# QPL9503.net
KiCad netlist of a schematic drawn in Altium Designer
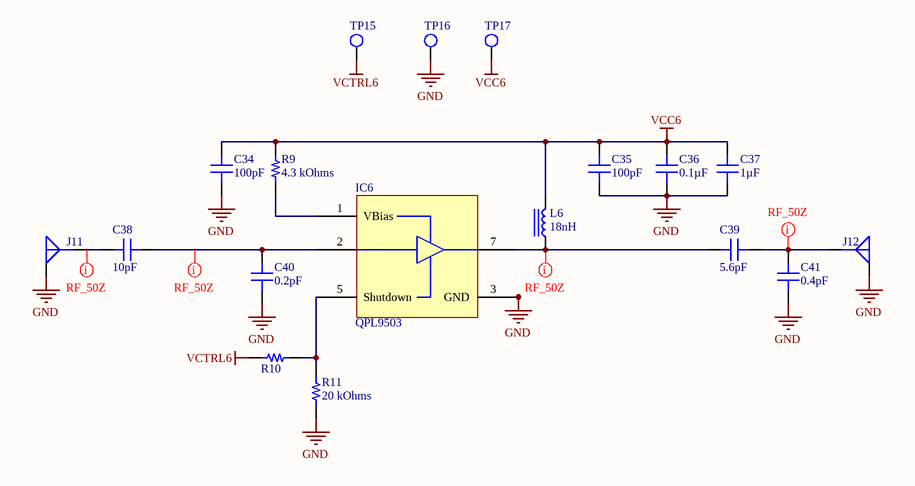
[diagram p0: QPL9503.SchDoc]

(export (version "E")
  (design (tool "Eeschema 10.0.6"))
  (components
    (comp (ref "C34")
      (value "100pF")
      (footprint "CAP 0402_1005")
      (description "CAP CER 100PF 50V C0G/NP0 0402")
      (fields
        (field (name "PART NUMBER") "GCM1555C1H101FA16D")
        (field (name "MANUFACTURER") "Murata Electronics")
      )
      (libsource (lib "Celestial Altium Library - altium_library") (part "Capacitor"))
    )
    (comp (ref "C35")
      (value "100pF")
      (footprint "CAP 0402_1005")
      (description "CAP CER 100PF 50V C0G/NP0 0402")
      (fields
        (field (name "PART NUMBER") "GCM1555C1H101FA16D")
        (field (name "MANUFACTURER") "Murata Electronics")
      )
      (libsource (lib "Celestial Altium Library - altium_library") (part "Capacitor"))
    )
    (comp (ref "C36")
      (value "0.1µF")
      (footprint "CAP 0402_1005")
      (description "CAP CER 0.1UF 16V X7R 0402")
      (fields (field (name "PART NUMBER") "EMK105B7104KV-F") (field (name "MANUFACTURER") "Taiyo Yuden"))
      (libsource (lib "Celestial Altium Library - altium_library") (part "Capacitor"))
    )
    (comp (ref "C37")
      (value "1µF")
      (footprint "CAP 0402_1005")
      (description "CAP CER 1UF 10V X5R 0402")
      (fields
        (field (name "PART NUMBER") "CL05A105KP5NNNC")
        (field (name "MANUFACTURER") "Samsung Electro-Mechanics")
      )
      (libsource (lib "Celestial Altium Library - altium_library") (part "Capacitor"))
    )
    (comp (ref "C38")
      (value "10pF")
      (footprint "CAP 0402_1005 RF")
      (description "CAP CER 10PF 50V C0G/NP0 0402")
      (fields
        (field (name "PART NUMBER") "GJM1555C1H100FB01D")
        (field (name "MANUFACTURER") "Murata Electronics")
      )
      (libsource (lib "Celestial Altium Library - altium_library") (part "Capacitor"))
    )
    (comp (ref "C39")
      (value "5.6pF")
      (footprint "CAP 0402_1005 RF")
      (description "CAP CER 5.6PF 50V C0G/NP0 0402")
      (fields
        (field (name "PART NUMBER") "GJM1555C1H5R6CB01D")
        (field (name "MANUFACTURER") "Murata Electronics")
      )
      (libsource (lib "Celestial Altium Library - altium_library") (part "Capacitor"))
    )
    (comp (ref "C40")
      (value "0.2pF")
      (footprint "CAP 0402_1005 RF")
      (description "CAP CER 0.2PF 50V C0G/NP0 0402")
      (fields
        (field (name "PART NUMBER") "GJM1555C1HR20WB01D")
        (field (name "MANUFACTURER") "Murata Electronics")
      )
      (libsource (lib "Celestial Altium Library - altium_library") (part "Capacitor"))
    )
    (comp (ref "C41")
      (value "0.4pF")
      (footprint "CAP 0402_1005 RF")
      (description "CAP CER 0.4PF 50V C0G/NP0 0402")
      (fields
        (field (name "PART NUMBER") "GJM1555C1HR40BB01D")
        (field (name "MANUFACTURER") "Murata Electronics")
      )
      (libsource (lib "Celestial Altium Library - altium_library") (part "Capacitor"))
    )
    (comp (ref "IC6")
      (value "QPL9503")
      (footprint "Qorvo LNA DFN-8 2X2")
      (description "Ultra Low-Noise, Flat Gain LNA")
      (libsource (lib "IC") (part "QPL9503"))
    )
    (comp (ref "J11")
      (value "CON-SMA-EDGE-S")
      (footprint "CON-SMA-EDGE-S")
      (description "CONN SMA JACK STR EDGE MNT")
      (libsource (lib "Connector") (part "CON-SMA-EDGE-S"))
    )
    (comp (ref "J12")
      (value "CON-SMA-EDGE-S")
      (footprint "CON-SMA-EDGE-S")
      (description "CONN SMA JACK STR EDGE MNT")
      (libsource (lib "Connector") (part "CON-SMA-EDGE-S"))
    )
    (comp (ref "L6")
      (value "18nH")
      (footprint "0402CS")
      (description "Fixed Inductors 1005 18nH Unshld 5% 420mA 230mOhms AECQ2")
      (libsource (lib "Inductor") (part "0402CS-18NXJLW"))
    )
    (comp (ref "R9")
      (value "4.3 kOhms")
      (footprint "RES 0402_1005")
      (description "RES SMD 4.3K OHM 1% 1/16W 0402")
      (fields (field (name "PART NUMBER") "RC0402FR-074K3L") (field (name "MANUFACTURER") "Yageo"))
      (libsource (lib "Celestial Altium Library - altium_library") (part "Resistor"))
    )
    (comp (ref "R10")
      (value "~")
      (footprint "RES 0402_1005")
      (description "RES SMD 0 OHM JUMPER 1/16W 0402")
      (fields (field (name "PART NUMBER") "RC0402JR-070RP") (field (name "MANUFACTURER") "Yageo"))
      (libsource (lib "Celestial Altium Library - altium_library") (part "Resistor"))
    )
    (comp (ref "R11")
      (value "20 kOhms")
      (footprint "RES 0402_1005")
      (description "RES SMD 20K OHM 1% 1/10W 0402")
      (fields
        (field (name "PART NUMBER") "ERJ-2RKF2002X")
        (field (name "MANUFACTURER") "Panasonic Electronic Components")
      )
      (libsource (lib "Celestial Altium Library - altium_library") (part "Resistor"))
    )
    (comp (ref "TP15")
      (value "Test Point-THM")
      (footprint "KEYSTONE-THM-TestPoint")
      (description "THRU HOLE MOUNT TEST POINTS")
      (libsource (lib "Misc") (part "Test Point-THM"))
    )
    (comp (ref "TP16")
      (value "Test Point-THM")
      (footprint "KEYSTONE-THM-TestPoint")
      (description "THRU HOLE MOUNT TEST POINTS")
      (libsource (lib "Misc") (part "Test Point-THM"))
    )
    (comp (ref "TP17")
      (value "Test Point-THM")
      (footprint "KEYSTONE-THM-TestPoint")
      (description "THRU HOLE MOUNT TEST POINTS")
      (libsource (lib "Misc") (part "Test Point-THM"))
    )
  )
  (nets
    (net (code "1") (name "GND") (class "Default")
      (node (ref "C34") (pin "2") (pinfunction "2_2") (pintype "passive"))
      (node (ref "C35") (pin "1") (pinfunction "1_1") (pintype "passive"))
      (node (ref "C36") (pin "1") (pinfunction "1_1") (pintype "passive"))
      (node (ref "C37") (pin "1") (pinfunction "1_1") (pintype "passive"))
      (node (ref "C40") (pin "1") (pinfunction "1_1") (pintype "passive"))
      (node (ref "C41") (pin "1") (pinfunction "1_1") (pintype "passive"))
      (node (ref "IC6") (pin "3") (pinfunction "GND_3") (pintype "passive"))
      (node (ref "IC6") (pin "4") (pinfunction "GND_4") (pintype "passive"))
      (node (ref "IC6") (pin "6") (pinfunction "GND_6") (pintype "passive"))
      (node (ref "IC6") (pin "8") (pinfunction "GND_8") (pintype "passive"))
      (node (ref "IC6") (pin "9") (pinfunction "GND_9") (pintype "passive"))
      (node (ref "J11") (pin "2") (pinfunction "G_2") (pintype "passive"))
      (node (ref "J12") (pin "2") (pinfunction "G_2") (pintype "passive"))
      (node (ref "R11") (pin "1") (pinfunction "1_1") (pintype "passive"))
      (node (ref "TP16") (pin "1") (pinfunction "TP_1") (pintype "passive"))
    )
    (net (code "2") (name "Net-(IC6-IN)") (class "Default")
      (node (ref "C38") (pin "2") (pinfunction "2_2") (pintype "passive"))
      (node (ref "C40") (pin "2") (pinfunction "2_2") (pintype "passive"))
      (node (ref "IC6") (pin "2") (pinfunction "IN_2") (pintype "passive"))
    )
    (net (code "3") (name "Net-(IC6-OUT)") (class "Default")
      (node (ref "C39") (pin "1") (pinfunction "1_1") (pintype "passive"))
      (node (ref "IC6") (pin "7") (pinfunction "OUT_7") (pintype "passive"))
      (node (ref "L6") (pin "1") (pinfunction "1_1") (pintype "passive"))
    )
    (net (code "4") (name "Net-(IC6-Shutdown)") (class "Default")
      (node (ref "IC6") (pin "5") (pinfunction "Shutdown_5") (pintype "passive"))
      (node (ref "R10") (pin "2") (pinfunction "2_2") (pintype "passive"))
      (node (ref "R11") (pin "2") (pinfunction "2_2") (pintype "passive"))
    )
    (net (code "5") (name "Net-(IC6-VBias)") (class "Default")
      (node (ref "IC6") (pin "1") (pinfunction "VBias_1") (pintype "passive"))
      (node (ref "R9") (pin "1") (pinfunction "1_1") (pintype "passive"))
    )
    (net (code "6") (name "Net-(J11-S)") (class "Default")
      (node (ref "C38") (pin "1") (pinfunction "1_1") (pintype "passive"))
      (node (ref "J11") (pin "1") (pinfunction "S_1") (pintype "passive"))
    )
    (net (code "7") (name "Net-(J12-S)") (class "Default")
      (node (ref "C39") (pin "2") (pinfunction "2_2") (pintype "passive"))
      (node (ref "C41") (pin "2") (pinfunction "2_2") (pintype "passive"))
      (node (ref "J12") (pin "1") (pinfunction "S_1") (pintype "passive"))
    )
    (net (code "8") (name "VCC6") (class "Default")
      (node (ref "C34") (pin "1") (pinfunction "1_1") (pintype "passive"))
      (node (ref "C35") (pin "2") (pinfunction "2_2") (pintype "passive"))
      (node (ref "C36") (pin "2") (pinfunction "2_2") (pintype "passive"))
      (node (ref "C37") (pin "2") (pinfunction "2_2") (pintype "passive"))
      (node (ref "L6") (pin "2") (pinfunction "2_2") (pintype "passive"))
      (node (ref "R9") (pin "2") (pinfunction "2_2") (pintype "passive"))
      (node (ref "TP17") (pin "1") (pinfunction "TP_1") (pintype "passive"))
    )
    (net (code "9") (name "VCTRL6") (class "Default")
      (node (ref "R10") (pin "1") (pinfunction "1_1") (pintype "passive"))
      (node (ref "TP15") (pin "1") (pinfunction "TP_1") (pintype "passive"))
    )
  )
)
